# PC_Power.net
KiCad netlist of a schematic drawn in Altium Designer
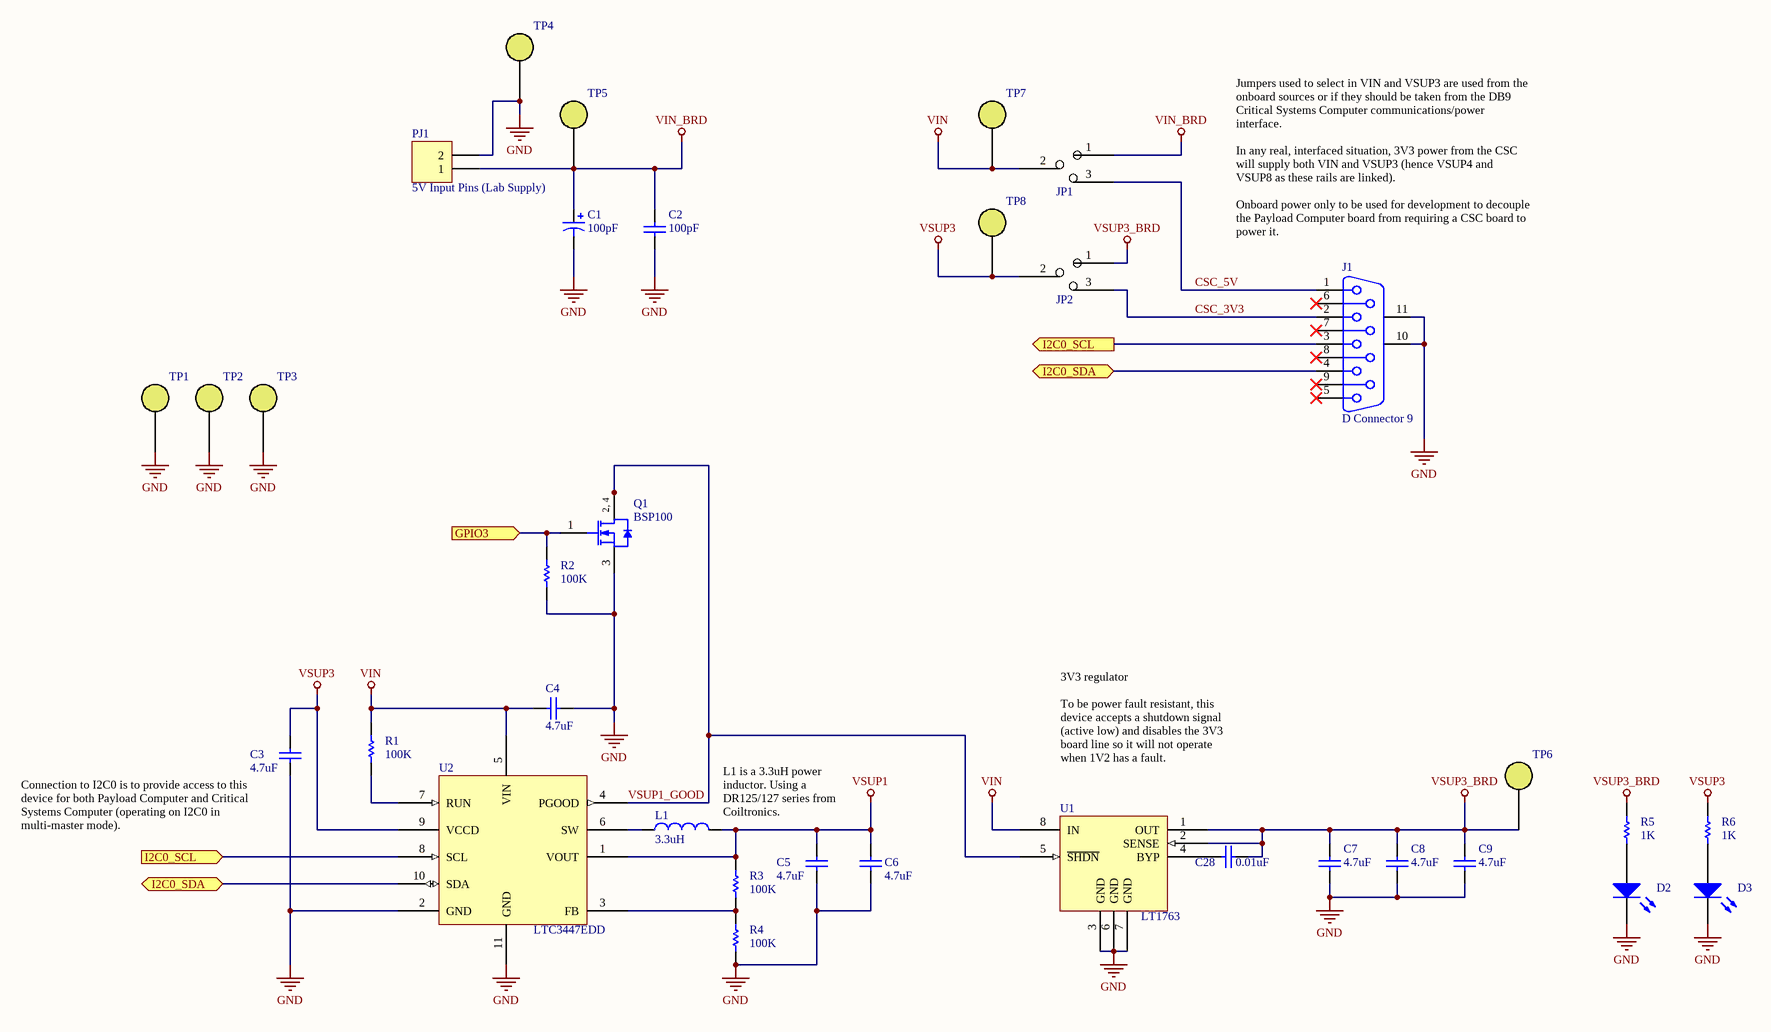
[diagram p0: PC_Power.SchDoc]

(export (version "E")
  (design (tool "Eeschema 10.0.6"))
  (components
    (comp (ref "C1")
      (value "100pF")
      (footprint "C0805")
      (description "Polarized Capacitor (Surface Mount)")
      (fields (field (name "Comment") "Cap Pol3") (field (name "PUBLISHER") "Altium Limited"))
      (libsource (lib "Miscellaneous Devices") (part "Cap Pol3"))
    )
    (comp (ref "C2")
      (value "100pF")
      (footprint "C0805")
      (description "Capacitor (Semiconductor SIM Model)")
      (fields (field (name "Comment") "Cap Semi") (field (name "PUBLISHER") "Altium Limited"))
      (libsource (lib "Miscellaneous Devices") (part "Cap Semi"))
    )
    (comp (ref "C3")
      (value "4.7uF")
      (footprint "C0805")
      (description "Capacitor (Semiconductor SIM Model)")
      (fields (field (name "Comment") "Cap Semi") (field (name "PUBLISHER") "Altium Limited"))
      (libsource (lib "Miscellaneous Devices") (part "Cap Semi"))
    )
    (comp (ref "C4")
      (value "4.7uF")
      (footprint "C0805")
      (description "Capacitor (Semiconductor SIM Model)")
      (fields (field (name "Comment") "Cap Semi") (field (name "PUBLISHER") "Altium Limited"))
      (libsource (lib "Miscellaneous Devices") (part "Cap Semi"))
    )
    (comp (ref "C5")
      (value "4.7uF")
      (footprint "C0805")
      (description "Capacitor (Semiconductor SIM Model)")
      (fields (field (name "Comment") "Cap Semi") (field (name "PUBLISHER") "Altium Limited"))
      (libsource (lib "Miscellaneous Devices") (part "Cap Semi"))
    )
    (comp (ref "C6")
      (value "4.7uF")
      (footprint "C0805")
      (description "Capacitor (Semiconductor SIM Model)")
      (fields (field (name "Comment") "Cap Semi") (field (name "PUBLISHER") "Altium Limited"))
      (libsource (lib "Miscellaneous Devices") (part "Cap Semi"))
    )
    (comp (ref "C7")
      (value "4.7uF")
      (footprint "C0805")
      (description "Capacitor (Semiconductor SIM Model)")
      (fields (field (name "Comment") "Cap Semi") (field (name "PUBLISHER") "Altium Limited"))
      (libsource (lib "Miscellaneous Devices") (part "Cap Semi"))
    )
    (comp (ref "C8")
      (value "4.7uF")
      (footprint "C0805")
      (description "Capacitor (Semiconductor SIM Model)")
      (fields (field (name "Comment") "Cap Semi") (field (name "PUBLISHER") "Altium Limited"))
      (libsource (lib "Miscellaneous Devices") (part "Cap Semi"))
    )
    (comp (ref "C9")
      (value "4.7uF")
      (footprint "C0805")
      (description "Capacitor (Semiconductor SIM Model)")
      (fields (field (name "Comment") "Cap Semi") (field (name "PUBLISHER") "Altium Limited"))
      (libsource (lib "Miscellaneous Devices") (part "Cap Semi"))
    )
    (comp (ref "C28")
      (value "0.01uF")
      (footprint "C0805")
      (description "Capacitor (Semiconductor SIM Model)")
      (fields (field (name "Comment") "Cap Semi") (field (name "PUBLISHER") "Altium Limited"))
      (libsource (lib "Miscellaneous Devices") (part "Cap Semi"))
    )
    (comp (ref "D2")
      (value "LED2")
      (footprint "DSO-F2/D6.1")
      (description "Typical RED, GREEN, YELLOW, AMBER GaAs LED")
      (fields (field (name "PUBLISHER") "Altium Limited"))
      (libsource (lib "Miscellaneous Devices") (part "LED2"))
    )
    (comp (ref "D3")
      (value "LED2")
      (footprint "DSO-F2/D6.1")
      (description "Typical RED, GREEN, YELLOW, AMBER GaAs LED")
      (fields (field (name "PUBLISHER") "Altium Limited"))
      (libsource (lib "Miscellaneous Devices") (part "LED2"))
    )
    (comp (ref "J1")
      (value "D Connector 9")
      (footprint "DSUB1.385-2H9")
      (description "Receptacle Assembly, 9 Position, Right Angle")
      (fields (field (name "PUBLISHER") "Altium Limited"))
      (libsource (lib "Miscellaneous Connectors") (part "D Connector 9"))
    )
    (comp (ref "JP1")
      (value "Jumper")
      (footprint "HDR1X3")
      (description "3 pin jumper for selection")
      (fields (field (name "PUBLISHER") "Altium Limited"))
      (libsource (lib "PC_Components") (part "2 position jumper"))
    )
    (comp (ref "JP2")
      (value "Jumper")
      (footprint "HDR1X3")
      (description "3 pin jumper for selection")
      (fields (field (name "PUBLISHER") "Altium Limited"))
      (libsource (lib "PC_Components") (part "2 position jumper"))
    )
    (comp (ref "L1")
      (value "3.3uH")
      (footprint "INDC13855X60N")
      (description "Inductor")
      (fields (field (name "PUBLISHER") "Altium Limited"))
      (libsource (lib "Miscellaneous Devices") (part "Inductor"))
    )
    (comp (ref "PJ1")
      (value "5V Input Pins (Lab Supply)")
      (footprint "HDR1X2")
      (description "Header, 2-Pin")
      (fields (field (name "PUBLISHER") "Altium Limited"))
      (libsource (lib "Miscellaneous Connectors") (part "Header 2"))
    )
    (comp (ref "Q1")
      (value "BSP100")
      (footprint "SOT223_N")
      (description "N-channel Enhancement Mode MOSFET")
      (fields (field (name "PUBLISHER") "Altium Limited"))
      (libsource (lib "Philips Discrete MOSFET - Power") (part "BSP100"))
    )
    (comp (ref "R1")
      (value "100K")
      (footprint "6-0805_L")
      (description "Semiconductor Resistor")
      (fields (field (name "Comment") "Res Semi") (field (name "PUBLISHER") "Altium Limited"))
      (libsource (lib "Miscellaneous Devices") (part "Res Semi"))
    )
    (comp (ref "R2")
      (value "100K")
      (footprint "6-0805_L")
      (description "Semiconductor Resistor")
      (fields (field (name "Comment") "Res Semi") (field (name "PUBLISHER") "Altium Limited"))
      (libsource (lib "Miscellaneous Devices") (part "Res Semi"))
    )
    (comp (ref "R3")
      (value "100K")
      (footprint "6-0805_L")
      (description "Semiconductor Resistor")
      (fields (field (name "Comment") "Res Semi") (field (name "PUBLISHER") "Altium Limited"))
      (libsource (lib "Miscellaneous Devices") (part "Res Semi"))
    )
    (comp (ref "R4")
      (value "100K")
      (footprint "6-0805_L")
      (description "Semiconductor Resistor")
      (fields (field (name "Comment") "Res Semi") (field (name "PUBLISHER") "Altium Limited"))
      (libsource (lib "Miscellaneous Devices") (part "Res Semi"))
    )
    (comp (ref "R5")
      (value "1K")
      (footprint "6-0805_L")
      (description "Semiconductor Resistor")
      (fields (field (name "Comment") "Res Semi") (field (name "PUBLISHER") "Altium Limited"))
      (libsource (lib "Miscellaneous Devices") (part "Res Semi"))
    )
    (comp (ref "R6")
      (value "1K")
      (footprint "6-0805_L")
      (description "Semiconductor Resistor")
      (fields (field (name "Comment") "Res Semi") (field (name "PUBLISHER") "Altium Limited"))
      (libsource (lib "Miscellaneous Devices") (part "Res Semi"))
    )
    (comp (ref "TP1")
      (value "Test Point")
      (footprint "PIN1")
      (description "Test point")
      (fields (field (name "PUBLISHER") "Altium Limited"))
      (libsource (lib "PC_Components") (part "Test Point"))
    )
    (comp (ref "TP2")
      (value "Test Point")
      (footprint "PIN1")
      (description "Test point")
      (fields (field (name "PUBLISHER") "Altium Limited"))
      (libsource (lib "PC_Components") (part "Test Point"))
    )
    (comp (ref "TP3")
      (value "Test Point")
      (footprint "PIN1")
      (description "Test point")
      (fields (field (name "PUBLISHER") "Altium Limited"))
      (libsource (lib "PC_Components") (part "Test Point"))
    )
    (comp (ref "TP4")
      (value "Test Point")
      (footprint "PIN1")
      (description "Test point")
      (fields (field (name "PUBLISHER") "Altium Limited"))
      (libsource (lib "PC_Components") (part "Test Point"))
    )
    (comp (ref "TP5")
      (value "Test Point")
      (footprint "PIN1")
      (description "Test point")
      (fields (field (name "PUBLISHER") "Altium Limited"))
      (libsource (lib "PC_Components") (part "Test Point"))
    )
    (comp (ref "TP6")
      (value "Test Point")
      (footprint "PIN1")
      (description "Test point")
      (fields (field (name "PUBLISHER") "Altium Limited"))
      (libsource (lib "PC_Components") (part "Test Point"))
    )
    (comp (ref "TP7")
      (value "Test Point")
      (footprint "PIN1")
      (description "Test point")
      (fields (field (name "PUBLISHER") "Altium Limited"))
      (libsource (lib "PC_Components") (part "Test Point"))
    )
    (comp (ref "TP8")
      (value "Test Point")
      (footprint "PIN1")
      (description "Test point")
      (fields (field (name "PUBLISHER") "Altium Limited"))
      (libsource (lib "PC_Components") (part "Test Point"))
    )
    (comp (ref "U1")
      (value "LT1763")
      (footprint "SOIC127P600X175-8N")
      (description "Linear Technology Voltage Regulator")
      (fields (field (name "PUBLISHER") "Altium Limited"))
      (libsource (lib "PC_Components") (part "LT1763"))
    )
    (comp (ref "U2")
      (value "LTC3447EDD")
      (footprint "LTC3447_DFP11")
      (description "I2C Controlled VReg")
      (fields (field (name "PUBLISHER") "Altium Limited"))
      (libsource (lib "PC_Components") (part "LTC3447EDD"))
    )
  )
  (nets
    (net (code "1") (name "/CSC_3V3") (class "Default")
      (node (ref "J1") (pin "2") (pinfunction "2_2") (pintype "passive"))
      (node (ref "JP2") (pin "3") (pinfunction "3_3") (pintype "passive"))
    )
    (net (code "2") (name "/CSC_5V") (class "Default")
      (node (ref "J1") (pin "1") (pinfunction "1_1") (pintype "passive"))
      (node (ref "JP1") (pin "3") (pinfunction "3_3") (pintype "passive"))
    )
    (net (code "3") (name "/GPIO3") (class "Default")
      (node (ref "Q1") (pin "1") (pinfunction "G_1") (pintype "passive"))
      (node (ref "R2") (pin "2") (pinfunction "2_2") (pintype "passive"))
    )
    (net (code "4") (name "/I2C0_SCL") (class "Default")
      (node (ref "J1") (pin "3") (pinfunction "3_3") (pintype "passive"))
      (node (ref "U2") (pin "8") (pinfunction "SCL_8") (pintype "input"))
    )
    (net (code "5") (name "/I2C0_SDA") (class "Default")
      (node (ref "J1") (pin "4") (pinfunction "4_4") (pintype "passive"))
      (node (ref "U2") (pin "10") (pinfunction "SDA_10") (pintype "bidirectional"))
    )
    (net (code "6") (name "/VSUP1_GOOD") (class "Default")
      (node (ref "Q1") (pin "2") (pinfunction "D_2") (pintype "passive"))
      (node (ref "Q1") (pin "4") (pinfunction "D_4") (pintype "passive"))
      (node (ref "U1") (pin "5") (pinfunction "~{SHDN}_5") (pintype "input"))
      (node (ref "U2") (pin "4") (pinfunction "PGOOD_4") (pintype "output"))
    )
    (net (code "7") (name "GND") (class "Default")
      (node (ref "C1") (pin "2") (pinfunction "2_2") (pintype "passive"))
      (node (ref "C2") (pin "1") (pinfunction "1_1") (pintype "passive"))
      (node (ref "C3") (pin "2") (pinfunction "2_2") (pintype "passive"))
      (node (ref "C4") (pin "1") (pinfunction "1_1") (pintype "passive"))
      (node (ref "C5") (pin "2") (pinfunction "2_2") (pintype "passive"))
      (node (ref "C6") (pin "2") (pinfunction "2_2") (pintype "passive"))
      (node (ref "C7") (pin "2") (pinfunction "2_2") (pintype "passive"))
      (node (ref "C8") (pin "2") (pinfunction "2_2") (pintype "passive"))
      (node (ref "C9") (pin "2") (pinfunction "2_2") (pintype "passive"))
      (node (ref "D2") (pin "2") (pinfunction "K_2") (pintype "passive"))
      (node (ref "D3") (pin "2") (pinfunction "K_2") (pintype "passive"))
      (node (ref "J1") (pin "10") (pinfunction "MH1_10") (pintype "passive"))
      (node (ref "J1") (pin "11") (pinfunction "MH2_11") (pintype "passive"))
      (node (ref "PJ1") (pin "2") (pinfunction "2_2") (pintype "passive"))
      (node (ref "Q1") (pin "3") (pinfunction "S_3") (pintype "passive"))
      (node (ref "R2") (pin "1") (pinfunction "1_1") (pintype "passive"))
      (node (ref "R4") (pin "1") (pinfunction "1_1") (pintype "passive"))
      (node (ref "TP1") (pin "1") (pinfunction "1_1") (pintype "passive"))
      (node (ref "TP2") (pin "1") (pinfunction "1_1") (pintype "passive"))
      (node (ref "TP3") (pin "1") (pinfunction "1_1") (pintype "passive"))
      (node (ref "TP4") (pin "1") (pinfunction "1_1") (pintype "passive"))
      (node (ref "U1") (pin "3") (pinfunction "GND_3") (pintype "power_in"))
      (node (ref "U1") (pin "6") (pinfunction "GND_6") (pintype "power_in"))
      (node (ref "U1") (pin "7") (pinfunction "GND_7") (pintype "power_in"))
      (node (ref "U2") (pin "11") (pinfunction "GND_11") (pintype "power_in"))
      (node (ref "U2") (pin "2") (pinfunction "GND_2") (pintype "power_in"))
    )
    (net (code "8") (name "Net-(D2-A)") (class "Default")
      (node (ref "D2") (pin "1") (pinfunction "A_1") (pintype "passive"))
      (node (ref "R5") (pin "1") (pinfunction "1_1") (pintype "passive"))
    )
    (net (code "9") (name "Net-(D3-A)") (class "Default")
      (node (ref "D3") (pin "1") (pinfunction "A_1") (pintype "passive"))
      (node (ref "R6") (pin "1") (pinfunction "1_1") (pintype "passive"))
    )
    (net (code "10") (name "Net-(U1-BYP)") (class "Default")
      (node (ref "C28") (pin "1") (pinfunction "1_1") (pintype "passive"))
      (node (ref "U1") (pin "4") (pinfunction "BYP_4") (pintype "passive"))
    )
    (net (code "11") (name "Net-(U2-FB)") (class "Default")
      (node (ref "R3") (pin "1") (pinfunction "1_1") (pintype "passive"))
      (node (ref "R4") (pin "2") (pinfunction "2_2") (pintype "passive"))
      (node (ref "U2") (pin "3") (pinfunction "FB_3") (pintype "open_collector"))
    )
    (net (code "12") (name "Net-(U2-RUN)") (class "Default")
      (node (ref "R1") (pin "1") (pinfunction "1_1") (pintype "passive"))
      (node (ref "U2") (pin "7") (pinfunction "RUN_7") (pintype "input"))
    )
    (net (code "13") (name "Net-(U2-SW)") (class "Default")
      (node (ref "L1") (pin "1") (pinfunction "1_1") (pintype "passive"))
      (node (ref "U2") (pin "6") (pinfunction "SW_6") (pintype "open_emitter"))
    )
    (net (code "14") (name "VIN") (class "Default")
      (node (ref "C4") (pin "2") (pinfunction "2_2") (pintype "passive"))
      (node (ref "JP1") (pin "2") (pinfunction "2_2") (pintype "passive"))
      (node (ref "R1") (pin "2") (pinfunction "2_2") (pintype "passive"))
      (node (ref "TP7") (pin "1") (pinfunction "1_1") (pintype "passive"))
      (node (ref "U1") (pin "8") (pinfunction "IN_8") (pintype "power_in"))
      (node (ref "U2") (pin "5") (pinfunction "VIN_5") (pintype "power_in"))
    )
    (net (code "15") (name "VIN_BRD") (class "Default")
      (node (ref "C1") (pin "1") (pinfunction "1_1") (pintype "passive"))
      (node (ref "C2") (pin "2") (pinfunction "2_2") (pintype "passive"))
      (node (ref "JP1") (pin "1") (pinfunction "1_1") (pintype "passive"))
      (node (ref "PJ1") (pin "1") (pinfunction "1_1") (pintype "passive"))
      (node (ref "TP5") (pin "1") (pinfunction "1_1") (pintype "passive"))
    )
    (net (code "16") (name "VSUP1") (class "Default")
      (node (ref "C5") (pin "1") (pinfunction "1_1") (pintype "passive"))
      (node (ref "C6") (pin "1") (pinfunction "1_1") (pintype "passive"))
      (node (ref "L1") (pin "2") (pinfunction "2_2") (pintype "passive"))
      (node (ref "R3") (pin "2") (pinfunction "2_2") (pintype "passive"))
      (node (ref "U2") (pin "1") (pinfunction "VOUT_1") (pintype "power_in"))
    )
    (net (code "17") (name "VSUP3") (class "Default")
      (node (ref "C3") (pin "1") (pinfunction "1_1") (pintype "passive"))
      (node (ref "JP2") (pin "2") (pinfunction "2_2") (pintype "passive"))
      (node (ref "R6") (pin "2") (pinfunction "2_2") (pintype "passive"))
      (node (ref "TP8") (pin "1") (pinfunction "1_1") (pintype "passive"))
      (node (ref "U2") (pin "9") (pinfunction "VCCD_9") (pintype "power_in"))
    )
    (net (code "18") (name "VSUP3_BRD") (class "Default")
      (node (ref "C28") (pin "2") (pinfunction "2_2") (pintype "passive"))
      (node (ref "C7") (pin "1") (pinfunction "1_1") (pintype "passive"))
      (node (ref "C8") (pin "1") (pinfunction "1_1") (pintype "passive"))
      (node (ref "C9") (pin "1") (pinfunction "1_1") (pintype "passive"))
      (node (ref "JP2") (pin "1") (pinfunction "1_1") (pintype "passive"))
      (node (ref "R5") (pin "2") (pinfunction "2_2") (pintype "passive"))
      (node (ref "TP6") (pin "1") (pinfunction "1_1") (pintype "passive"))
      (node (ref "U1") (pin "1") (pinfunction "OUT_1") (pintype "power_in"))
      (node (ref "U1") (pin "2") (pinfunction "SENSE_2") (pintype "input"))
    )
    (net (code "19") (name "unconnected-(J1-Pad5)") (class "Default")
      (node (ref "J1") (pin "5") (pinfunction "5_5") (pintype "passive+no_connect"))
    )
    (net (code "20") (name "unconnected-(J1-Pad6)") (class "Default")
      (node (ref "J1") (pin "6") (pinfunction "6_6") (pintype "passive+no_connect"))
    )
    (net (code "21") (name "unconnected-(J1-Pad7)") (class "Default")
      (node (ref "J1") (pin "7") (pinfunction "7_7") (pintype "passive+no_connect"))
    )
    (net (code "22") (name "unconnected-(J1-Pad8)") (class "Default")
      (node (ref "J1") (pin "8") (pinfunction "8_8") (pintype "passive+no_connect"))
    )
    (net (code "23") (name "unconnected-(J1-Pad9)") (class "Default")
      (node (ref "J1") (pin "9") (pinfunction "9_9") (pintype "passive+no_connect"))
    )
  )
)
